# ColorsoundPowerBooster.net
KiCad netlist of a schematic drawn in EAGLE
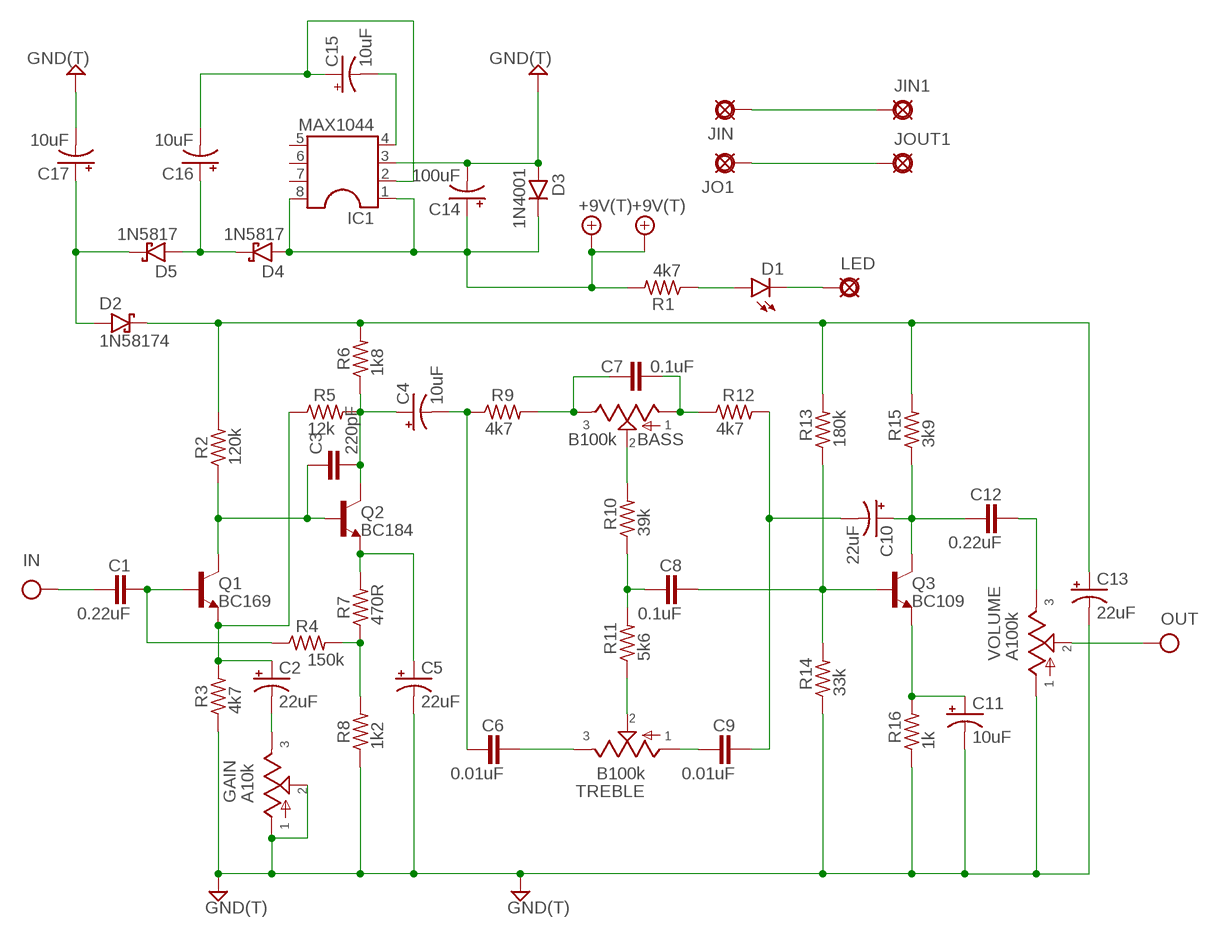
[diagram p0: schematic, sheet 1]

(export (version "E")
  (design (tool "Eeschema 10.0.6"))
  (components
    (comp (ref "+9V")
      (value "+9V(T)")
      (footprint "eagle-import:SQUARE")
      (libsource (lib "eagle-import") (part "+9V(T)"))
    )
    (comp (ref "+9V1")
      (value "+9V(T)")
      (footprint "eagle-import:SQUARE")
      (libsource (lib "eagle-import") (part "+9V(T)"))
    )
    (comp (ref "BASS")
      (value "B100k")
      (footprint "eagle-import:16MM")
      (libsource (lib "eagle-import") (part "POT16MM"))
    )
    (comp (ref "C1")
      (value "0.22uF")
      (footprint "eagle-import:072X025")
      (libsource (lib "eagle-import") (part "072X0252"))
    )
    (comp (ref "C2")
      (value "22uF")
      (footprint "eagle-import:050_020_1")
      (libsource (lib "eagle-import") (part "0501"))
    )
    (comp (ref "C3")
      (value "220pF")
      (footprint "eagle-import:050X030_025")
      (libsource (lib "eagle-import") (part "050X030_0251"))
    )
    (comp (ref "C4")
      (value "10uF")
      (footprint "eagle-import:050_020_1")
      (libsource (lib "eagle-import") (part "0501"))
    )
    (comp (ref "C5")
      (value "22uF")
      (footprint "eagle-import:050_020_1")
      (libsource (lib "eagle-import") (part "0501"))
    )
    (comp (ref "C6")
      (value "0.01uF")
      (footprint "eagle-import:072X025")
      (libsource (lib "eagle-import") (part "072X0252"))
    )
    (comp (ref "C7")
      (value "0.1uF")
      (footprint "eagle-import:072X025")
      (libsource (lib "eagle-import") (part "072X0252"))
    )
    (comp (ref "C8")
      (value "0.1uF")
      (footprint "eagle-import:072X025")
      (libsource (lib "eagle-import") (part "072X0252"))
    )
    (comp (ref "C9")
      (value "0.01uF")
      (footprint "eagle-import:072X025")
      (libsource (lib "eagle-import") (part "072X0252"))
    )
    (comp (ref "C10")
      (value "22uF")
      (footprint "eagle-import:050_020_1")
      (libsource (lib "eagle-import") (part "0501"))
    )
    (comp (ref "C11")
      (value "10uF")
      (footprint "eagle-import:050_020_1")
      (libsource (lib "eagle-import") (part "0501"))
    )
    (comp (ref "C12")
      (value "0.22uF")
      (footprint "eagle-import:072X025")
      (libsource (lib "eagle-import") (part "072X0252"))
    )
    (comp (ref "C13")
      (value "22uF")
      (footprint "eagle-import:050_020_1")
      (libsource (lib "eagle-import") (part "0501"))
    )
    (comp (ref "C14")
      (value "100uF")
      (footprint "eagle-import:080_035_1")
      (libsource (lib "eagle-import") (part "0801"))
    )
    (comp (ref "C15")
      (value "10uF")
      (footprint "eagle-import:050_020_1")
      (libsource (lib "eagle-import") (part "0501"))
    )
    (comp (ref "C16")
      (value "10uF")
      (footprint "eagle-import:050_020_1")
      (libsource (lib "eagle-import") (part "0501"))
    )
    (comp (ref "C17")
      (value "10uF")
      (footprint "eagle-import:050_020_1")
      (libsource (lib "eagle-import") (part "0501"))
    )
    (comp (ref "D1")
      (value "LED")
      (footprint "eagle-import:LED3MM")
      (libsource (lib "eagle-import") (part "LED3MM"))
    )
    (comp (ref "D2")
      (value "1N58174")
      (footprint "eagle-import:DO41-4")
      (libsource (lib "eagle-import") (part "1N58174"))
    )
    (comp (ref "D3")
      (value "1N4001")
      (footprint "eagle-import:DO41-3")
      (libsource (lib "eagle-import") (part "1N400X.3"))
    )
    (comp (ref "D4")
      (value "1N5817")
      (footprint "eagle-import:DO41-3")
      (libsource (lib "eagle-import") (part "1N5817"))
    )
    (comp (ref "D5")
      (value "1N5817")
      (footprint "eagle-import:DO41-3")
      (libsource (lib "eagle-import") (part "1N5817"))
    )
    (comp (ref "G")
      (value "GND(T)")
      (footprint "eagle-import:SQUARE")
      (libsource (lib "eagle-import") (part "GND(T)"))
    )
    (comp (ref "G6")
      (value "GND(T)")
      (footprint "eagle-import:SQUARE")
      (libsource (lib "eagle-import") (part "GND(T)"))
    )
    (comp (ref "GAIN")
      (value "A10k")
      (footprint "eagle-import:16MM")
      (libsource (lib "eagle-import") (part "POT16MM"))
    )
    (comp (ref "IC1")
      (value "MAX1044")
      (footprint "eagle-import:DIL08")
      (libsource (lib "eagle-import") (part "MAX1044"))
    )
    (comp (ref "IN")
      (value "IN(T)")
      (footprint "eagle-import:SQUARE")
      (libsource (lib "eagle-import") (part "IN(T)"))
    )
    (comp (ref "JIG")
      (value "GND(T)")
      (footprint "eagle-import:SQUARE")
      (libsource (lib "eagle-import") (part "GND(T)"))
    )
    (comp (ref "JIN")
      (value "PAD")
      (footprint "eagle-import:SQUARE")
      (libsource (lib "eagle-import") (part "PAD"))
    )
    (comp (ref "JIN1")
      (value "PAD")
      (footprint "eagle-import:SQUARE")
      (libsource (lib "eagle-import") (part "PAD"))
    )
    (comp (ref "JO1")
      (value "PAD")
      (footprint "eagle-import:SQUARE")
      (libsource (lib "eagle-import") (part "PAD"))
    )
    (comp (ref "JOG")
      (value "GND(T)")
      (footprint "eagle-import:SQUARE")
      (libsource (lib "eagle-import") (part "GND(T)"))
    )
    (comp (ref "JOUT1")
      (value "PAD")
      (footprint "eagle-import:SQUARE")
      (libsource (lib "eagle-import") (part "PAD"))
    )
    (comp (ref "LED")
      (value "PAD")
      (footprint "eagle-import:SQUARE")
      (libsource (lib "eagle-import") (part "PAD"))
    )
    (comp (ref "OUT")
      (value "OUT(T)")
      (footprint "eagle-import:SQUARE")
      (libsource (lib "eagle-import") (part "OUT(T)"))
    )
    (comp (ref "Q1")
      (value "BC169")
      (footprint "eagle-import:TO92-")
      (libsource (lib "eagle-import") (part "BC109"))
    )
    (comp (ref "Q2")
      (value "BC184")
      (footprint "eagle-import:TO92-")
      (libsource (lib "eagle-import") (part "BC109"))
    )
    (comp (ref "Q3")
      (value "BC109")
      (footprint "eagle-import:TO92-")
      (libsource (lib "eagle-import") (part "BC109"))
    )
    (comp (ref "R1")
      (value "4k7")
      (footprint "eagle-import:R0207_3")
      (libsource (lib "eagle-import") (part "6MM.3"))
    )
    (comp (ref "R2")
      (value "120k")
      (footprint "eagle-import:R0207_3")
      (libsource (lib "eagle-import") (part "6MM.3"))
    )
    (comp (ref "R3")
      (value "4k7")
      (footprint "eagle-import:R0207_3")
      (libsource (lib "eagle-import") (part "6MM.3"))
    )
    (comp (ref "R4")
      (value "150k")
      (footprint "eagle-import:R0207_3")
      (libsource (lib "eagle-import") (part "6MM.3"))
    )
    (comp (ref "R5")
      (value "12k")
      (footprint "eagle-import:R0207_3")
      (libsource (lib "eagle-import") (part "6MM.3"))
    )
    (comp (ref "R6")
      (value "1k8")
      (footprint "eagle-import:R0207_3")
      (libsource (lib "eagle-import") (part "6MM.3"))
    )
    (comp (ref "R7")
      (value "470R")
      (footprint "eagle-import:R0207_3")
      (libsource (lib "eagle-import") (part "6MM.3"))
    )
    (comp (ref "R8")
      (value "1k2")
      (footprint "eagle-import:R0207_3")
      (libsource (lib "eagle-import") (part "6MM.3"))
    )
    (comp (ref "R9")
      (value "4k7")
      (footprint "eagle-import:R0207_3")
      (libsource (lib "eagle-import") (part "6MM.3"))
    )
    (comp (ref "R10")
      (value "39k")
      (footprint "eagle-import:R0207_3")
      (libsource (lib "eagle-import") (part "6MM.3"))
    )
    (comp (ref "R11")
      (value "5k6")
      (footprint "eagle-import:R0207_3")
      (libsource (lib "eagle-import") (part "6MM.3"))
    )
    (comp (ref "R12")
      (value "4k7")
      (footprint "eagle-import:R0207_3")
      (libsource (lib "eagle-import") (part "6MM.3"))
    )
    (comp (ref "R13")
      (value "180k")
      (footprint "eagle-import:R0207_3")
      (libsource (lib "eagle-import") (part "6MM.3"))
    )
    (comp (ref "R14")
      (value "33k")
      (footprint "eagle-import:R0207_3")
      (libsource (lib "eagle-import") (part "6MM.3"))
    )
    (comp (ref "R15")
      (value "3k9")
      (footprint "eagle-import:R0207_3")
      (libsource (lib "eagle-import") (part "6MM.3"))
    )
    (comp (ref "R16")
      (value "1k")
      (footprint "eagle-import:R0207_3")
      (libsource (lib "eagle-import") (part "6MM.3"))
    )
    (comp (ref "TREBLE")
      (value "B100k")
      (footprint "eagle-import:16MM")
      (libsource (lib "eagle-import") (part "POT16MM"))
    )
    (comp (ref "VOLUME")
      (value "A100k")
      (footprint "eagle-import:16MM")
      (libsource (lib "eagle-import") (part "POT16MM"))
    )
  )
  (nets
    (net (code "1") (name "+9V(T)") (class "Default")
      (node (ref "+9V") (pin "1") (pinfunction "+9V_1") (pintype "power_in"))
      (node (ref "+9V1") (pin "1") (pinfunction "+9V_1") (pintype "power_in"))
      (node (ref "C14") (pin "+") (pinfunction "+_+") (pintype "passive"))
      (node (ref "D3") (pin "C") (pinfunction "C_C") (pintype "passive"))
      (node (ref "D4") (pin "A") (pinfunction "A_A") (pintype "passive"))
      (node (ref "IC1") (pin "1") (pinfunction "1_1") (pintype "passive"))
      (node (ref "IC1") (pin "8") (pinfunction "8_8") (pintype "passive"))
      (node (ref "R1") (pin "2") (pinfunction "2_2") (pintype "passive"))
    )
    (net (code "2") (name "GND(T)") (class "Default")
      (node (ref "C11") (pin "-") (pinfunction "-_-") (pintype "passive"))
      (node (ref "C13") (pin "-") (pinfunction "-_-") (pintype "passive"))
      (node (ref "C14") (pin "-") (pinfunction "-_-") (pintype "passive"))
      (node (ref "C17") (pin "-") (pinfunction "-_-") (pintype "passive"))
      (node (ref "C5") (pin "-") (pinfunction "-_-") (pintype "passive"))
      (node (ref "D3") (pin "A") (pinfunction "A_A") (pintype "passive"))
      (node (ref "G") (pin "1") (pinfunction "GND_1") (pintype "power_in"))
      (node (ref "G6") (pin "1") (pinfunction "GND_1") (pintype "power_in"))
      (node (ref "GAIN") (pin "1") (pinfunction "1_1") (pintype "passive"))
      (node (ref "GAIN") (pin "2") (pinfunction "2_2") (pintype "passive"))
      (node (ref "IC1") (pin "3") (pinfunction "3_3") (pintype "passive"))
      (node (ref "JIG") (pin "1") (pinfunction "GND_1") (pintype "power_in"))
      (node (ref "JOG") (pin "1") (pinfunction "GND_1") (pintype "power_in"))
      (node (ref "R14") (pin "1") (pinfunction "1_1") (pintype "passive"))
      (node (ref "R16") (pin "1") (pinfunction "1_1") (pintype "passive"))
      (node (ref "R3") (pin "1") (pinfunction "1_1") (pintype "passive"))
      (node (ref "R8") (pin "1") (pinfunction "1_1") (pintype "passive"))
      (node (ref "VOLUME") (pin "1") (pinfunction "1_1") (pintype "passive"))
    )
    (net (code "3") (name "IN(T)") (class "Default")
      (node (ref "C1") (pin "1") (pinfunction "1_1") (pintype "passive"))
      (node (ref "IN") (pin "1") (pinfunction "IN_1") (pintype "power_in"))
    )
    (net (code "4") (name "Net-(BASS-Pad1)") (class "Default")
      (node (ref "BASS") (pin "1") (pinfunction "1_1") (pintype "passive"))
      (node (ref "C7") (pin "2") (pinfunction "2_2") (pintype "passive"))
      (node (ref "R12") (pin "1") (pinfunction "1_1") (pintype "passive"))
    )
    (net (code "5") (name "Net-(BASS-Pad2)") (class "Default")
      (node (ref "BASS") (pin "2") (pinfunction "2_2") (pintype "passive"))
      (node (ref "R10") (pin "2") (pinfunction "2_2") (pintype "passive"))
    )
    (net (code "6") (name "Net-(BASS-Pad3)") (class "Default")
      (node (ref "BASS") (pin "3") (pinfunction "3_3") (pintype "passive"))
      (node (ref "C7") (pin "1") (pinfunction "1_1") (pintype "passive"))
      (node (ref "R9") (pin "2") (pinfunction "2_2") (pintype "passive"))
    )
    (net (code "7") (name "Net-(C2-Pad-)") (class "Default")
      (node (ref "C2") (pin "-") (pinfunction "-_-") (pintype "passive"))
      (node (ref "GAIN") (pin "3") (pinfunction "3_3") (pintype "passive"))
    )
    (net (code "8") (name "Net-(C4-Pad-)") (class "Default")
      (node (ref "C4") (pin "-") (pinfunction "-_-") (pintype "passive"))
      (node (ref "C6") (pin "1") (pinfunction "1_1") (pintype "passive"))
      (node (ref "R9") (pin "1") (pinfunction "1_1") (pintype "passive"))
    )
    (net (code "9") (name "Net-(C6-Pad2)") (class "Default")
      (node (ref "C6") (pin "2") (pinfunction "2_2") (pintype "passive"))
      (node (ref "TREBLE") (pin "3") (pinfunction "3_3") (pintype "passive"))
    )
    (net (code "10") (name "Net-(C8-Pad1)") (class "Default")
      (node (ref "C8") (pin "1") (pinfunction "1_1") (pintype "passive"))
      (node (ref "R10") (pin "1") (pinfunction "1_1") (pintype "passive"))
      (node (ref "R11") (pin "2") (pinfunction "2_2") (pintype "passive"))
    )
    (net (code "11") (name "Net-(C9-Pad1)") (class "Default")
      (node (ref "C9") (pin "1") (pinfunction "1_1") (pintype "passive"))
      (node (ref "TREBLE") (pin "1") (pinfunction "1_1") (pintype "passive"))
    )
    (net (code "12") (name "Net-(C10-Pad-)") (class "Default")
      (node (ref "C10") (pin "-") (pinfunction "-_-") (pintype "passive"))
      (node (ref "C9") (pin "2") (pinfunction "2_2") (pintype "passive"))
      (node (ref "R12") (pin "2") (pinfunction "2_2") (pintype "passive"))
    )
    (net (code "13") (name "Net-(C12-Pad2)") (class "Default")
      (node (ref "C12") (pin "2") (pinfunction "2_2") (pintype "passive"))
      (node (ref "VOLUME") (pin "3") (pinfunction "3_3") (pintype "passive"))
    )
    (net (code "14") (name "Net-(C13-Pad+)") (class "Default")
      (node (ref "C13") (pin "+") (pinfunction "+_+") (pintype "passive"))
      (node (ref "D2") (pin "C") (pinfunction "C_C") (pintype "passive"))
      (node (ref "R13") (pin "2") (pinfunction "2_2") (pintype "passive"))
      (node (ref "R15") (pin "2") (pinfunction "2_2") (pintype "passive"))
      (node (ref "R2") (pin "2") (pinfunction "2_2") (pintype "passive"))
      (node (ref "R6") (pin "2") (pinfunction "2_2") (pintype "passive"))
    )
    (net (code "15") (name "Net-(C15-Pad+)") (class "Default")
      (node (ref "C15") (pin "+") (pinfunction "+_+") (pintype "passive"))
      (node (ref "C16") (pin "-") (pinfunction "-_-") (pintype "passive"))
      (node (ref "IC1") (pin "2") (pinfunction "2_2") (pintype "passive"))
    )
    (net (code "16") (name "Net-(C15-Pad-)") (class "Default")
      (node (ref "C15") (pin "-") (pinfunction "-_-") (pintype "passive"))
      (node (ref "IC1") (pin "4") (pinfunction "4_4") (pintype "passive"))
    )
    (net (code "17") (name "Net-(C16-Pad+)") (class "Default")
      (node (ref "C16") (pin "+") (pinfunction "+_+") (pintype "passive"))
      (node (ref "D4") (pin "C") (pinfunction "C_C") (pintype "passive"))
      (node (ref "D5") (pin "A") (pinfunction "A_A") (pintype "passive"))
    )
    (net (code "18") (name "Net-(C17-Pad+)") (class "Default")
      (node (ref "C17") (pin "+") (pinfunction "+_+") (pintype "passive"))
      (node (ref "D2") (pin "A") (pinfunction "A_A") (pintype "passive"))
      (node (ref "D5") (pin "C") (pinfunction "C_C") (pintype "passive"))
    )
    (net (code "19") (name "Net-(D1-C)") (class "Default")
      (node (ref "D1") (pin "K") (pinfunction "C_K") (pintype "passive"))
      (node (ref "LED") (pin "1") (pinfunction "PAD_1") (pintype "passive"))
    )
    (net (code "20") (name "Net-(D1-PadA)") (class "Default")
      (node (ref "D1") (pin "A") (pinfunction "A_A") (pintype "passive"))
      (node (ref "R1") (pin "1") (pinfunction "1_1") (pintype "passive"))
    )
    (net (code "21") (name "Net-(JIN-PAD)") (class "Default")
      (node (ref "JIN") (pin "1") (pinfunction "PAD_1") (pintype "passive"))
      (node (ref "JIN1") (pin "1") (pinfunction "PAD_1") (pintype "passive"))
    )
    (net (code "22") (name "Net-(JO1-PAD)") (class "Default")
      (node (ref "JO1") (pin "1") (pinfunction "PAD_1") (pintype "passive"))
      (node (ref "JOUT1") (pin "1") (pinfunction "PAD_1") (pintype "passive"))
    )
    (net (code "23") (name "Net-(Q1-B)") (class "Default")
      (node (ref "C1") (pin "2") (pinfunction "2_2") (pintype "passive"))
      (node (ref "Q1") (pin "2") (pinfunction "B_2") (pintype "passive"))
      (node (ref "R4") (pin "1") (pinfunction "1_1") (pintype "passive"))
    )
    (net (code "24") (name "Net-(Q1-C)") (class "Default")
      (node (ref "C3") (pin "1") (pinfunction "1_1") (pintype "passive"))
      (node (ref "Q1") (pin "3") (pinfunction "C_3") (pintype "passive"))
      (node (ref "Q2") (pin "2") (pinfunction "B_2") (pintype "passive"))
      (node (ref "R2") (pin "1") (pinfunction "1_1") (pintype "passive"))
    )
    (net (code "25") (name "Net-(Q1-E)") (class "Default")
      (node (ref "C2") (pin "+") (pinfunction "+_+") (pintype "passive"))
      (node (ref "Q1") (pin "1") (pinfunction "E_1") (pintype "passive"))
      (node (ref "R3") (pin "2") (pinfunction "2_2") (pintype "passive"))
      (node (ref "R5") (pin "1") (pinfunction "1_1") (pintype "passive"))
    )
    (net (code "26") (name "Net-(Q2-C)") (class "Default")
      (node (ref "C3") (pin "2") (pinfunction "2_2") (pintype "passive"))
      (node (ref "C4") (pin "+") (pinfunction "+_+") (pintype "passive"))
      (node (ref "Q2") (pin "3") (pinfunction "C_3") (pintype "passive"))
      (node (ref "R5") (pin "2") (pinfunction "2_2") (pintype "passive"))
      (node (ref "R6") (pin "1") (pinfunction "1_1") (pintype "passive"))
    )
    (net (code "27") (name "Net-(Q2-E)") (class "Default")
      (node (ref "C5") (pin "+") (pinfunction "+_+") (pintype "passive"))
      (node (ref "Q2") (pin "1") (pinfunction "E_1") (pintype "passive"))
      (node (ref "R7") (pin "2") (pinfunction "2_2") (pintype "passive"))
    )
    (net (code "28") (name "Net-(Q3-B)") (class "Default")
      (node (ref "C8") (pin "2") (pinfunction "2_2") (pintype "passive"))
      (node (ref "Q3") (pin "2") (pinfunction "B_2") (pintype "passive"))
      (node (ref "R13") (pin "1") (pinfunction "1_1") (pintype "passive"))
      (node (ref "R14") (pin "2") (pinfunction "2_2") (pintype "passive"))
    )
    (net (code "29") (name "Net-(Q3-C)") (class "Default")
      (node (ref "C10") (pin "+") (pinfunction "+_+") (pintype "passive"))
      (node (ref "C12") (pin "1") (pinfunction "1_1") (pintype "passive"))
      (node (ref "Q3") (pin "3") (pinfunction "C_3") (pintype "passive"))
      (node (ref "R15") (pin "1") (pinfunction "1_1") (pintype "passive"))
    )
    (net (code "30") (name "Net-(Q3-E)") (class "Default")
      (node (ref "C11") (pin "+") (pinfunction "+_+") (pintype "passive"))
      (node (ref "Q3") (pin "1") (pinfunction "E_1") (pintype "passive"))
      (node (ref "R16") (pin "2") (pinfunction "2_2") (pintype "passive"))
    )
    (net (code "31") (name "Net-(R4-Pad2)") (class "Default")
      (node (ref "R4") (pin "2") (pinfunction "2_2") (pintype "passive"))
      (node (ref "R7") (pin "1") (pinfunction "1_1") (pintype "passive"))
      (node (ref "R8") (pin "2") (pinfunction "2_2") (pintype "passive"))
    )
    (net (code "32") (name "Net-(R11-Pad1)") (class "Default")
      (node (ref "R11") (pin "1") (pinfunction "1_1") (pintype "passive"))
      (node (ref "TREBLE") (pin "2") (pinfunction "2_2") (pintype "passive"))
    )
    (net (code "33") (name "OUT(T)") (class "Default")
      (node (ref "OUT") (pin "1") (pinfunction "OUT_1") (pintype "power_in"))
      (node (ref "VOLUME") (pin "2") (pinfunction "2_2") (pintype "passive"))
    )
    (net (code "34") (name "unconnected-(IC1-Pad5)") (class "Default")
      (node (ref "IC1") (pin "5") (pinfunction "5_5") (pintype "passive"))
    )
    (net (code "35") (name "unconnected-(IC1-Pad6)") (class "Default")
      (node (ref "IC1") (pin "6") (pinfunction "6_6") (pintype "passive"))
    )
    (net (code "36") (name "unconnected-(IC1-Pad7)") (class "Default")
      (node (ref "IC1") (pin "7") (pinfunction "7_7") (pintype "passive"))
    )
  )
)
